# openx3.net
KiCad netlist of a schematic drawn in EAGLE
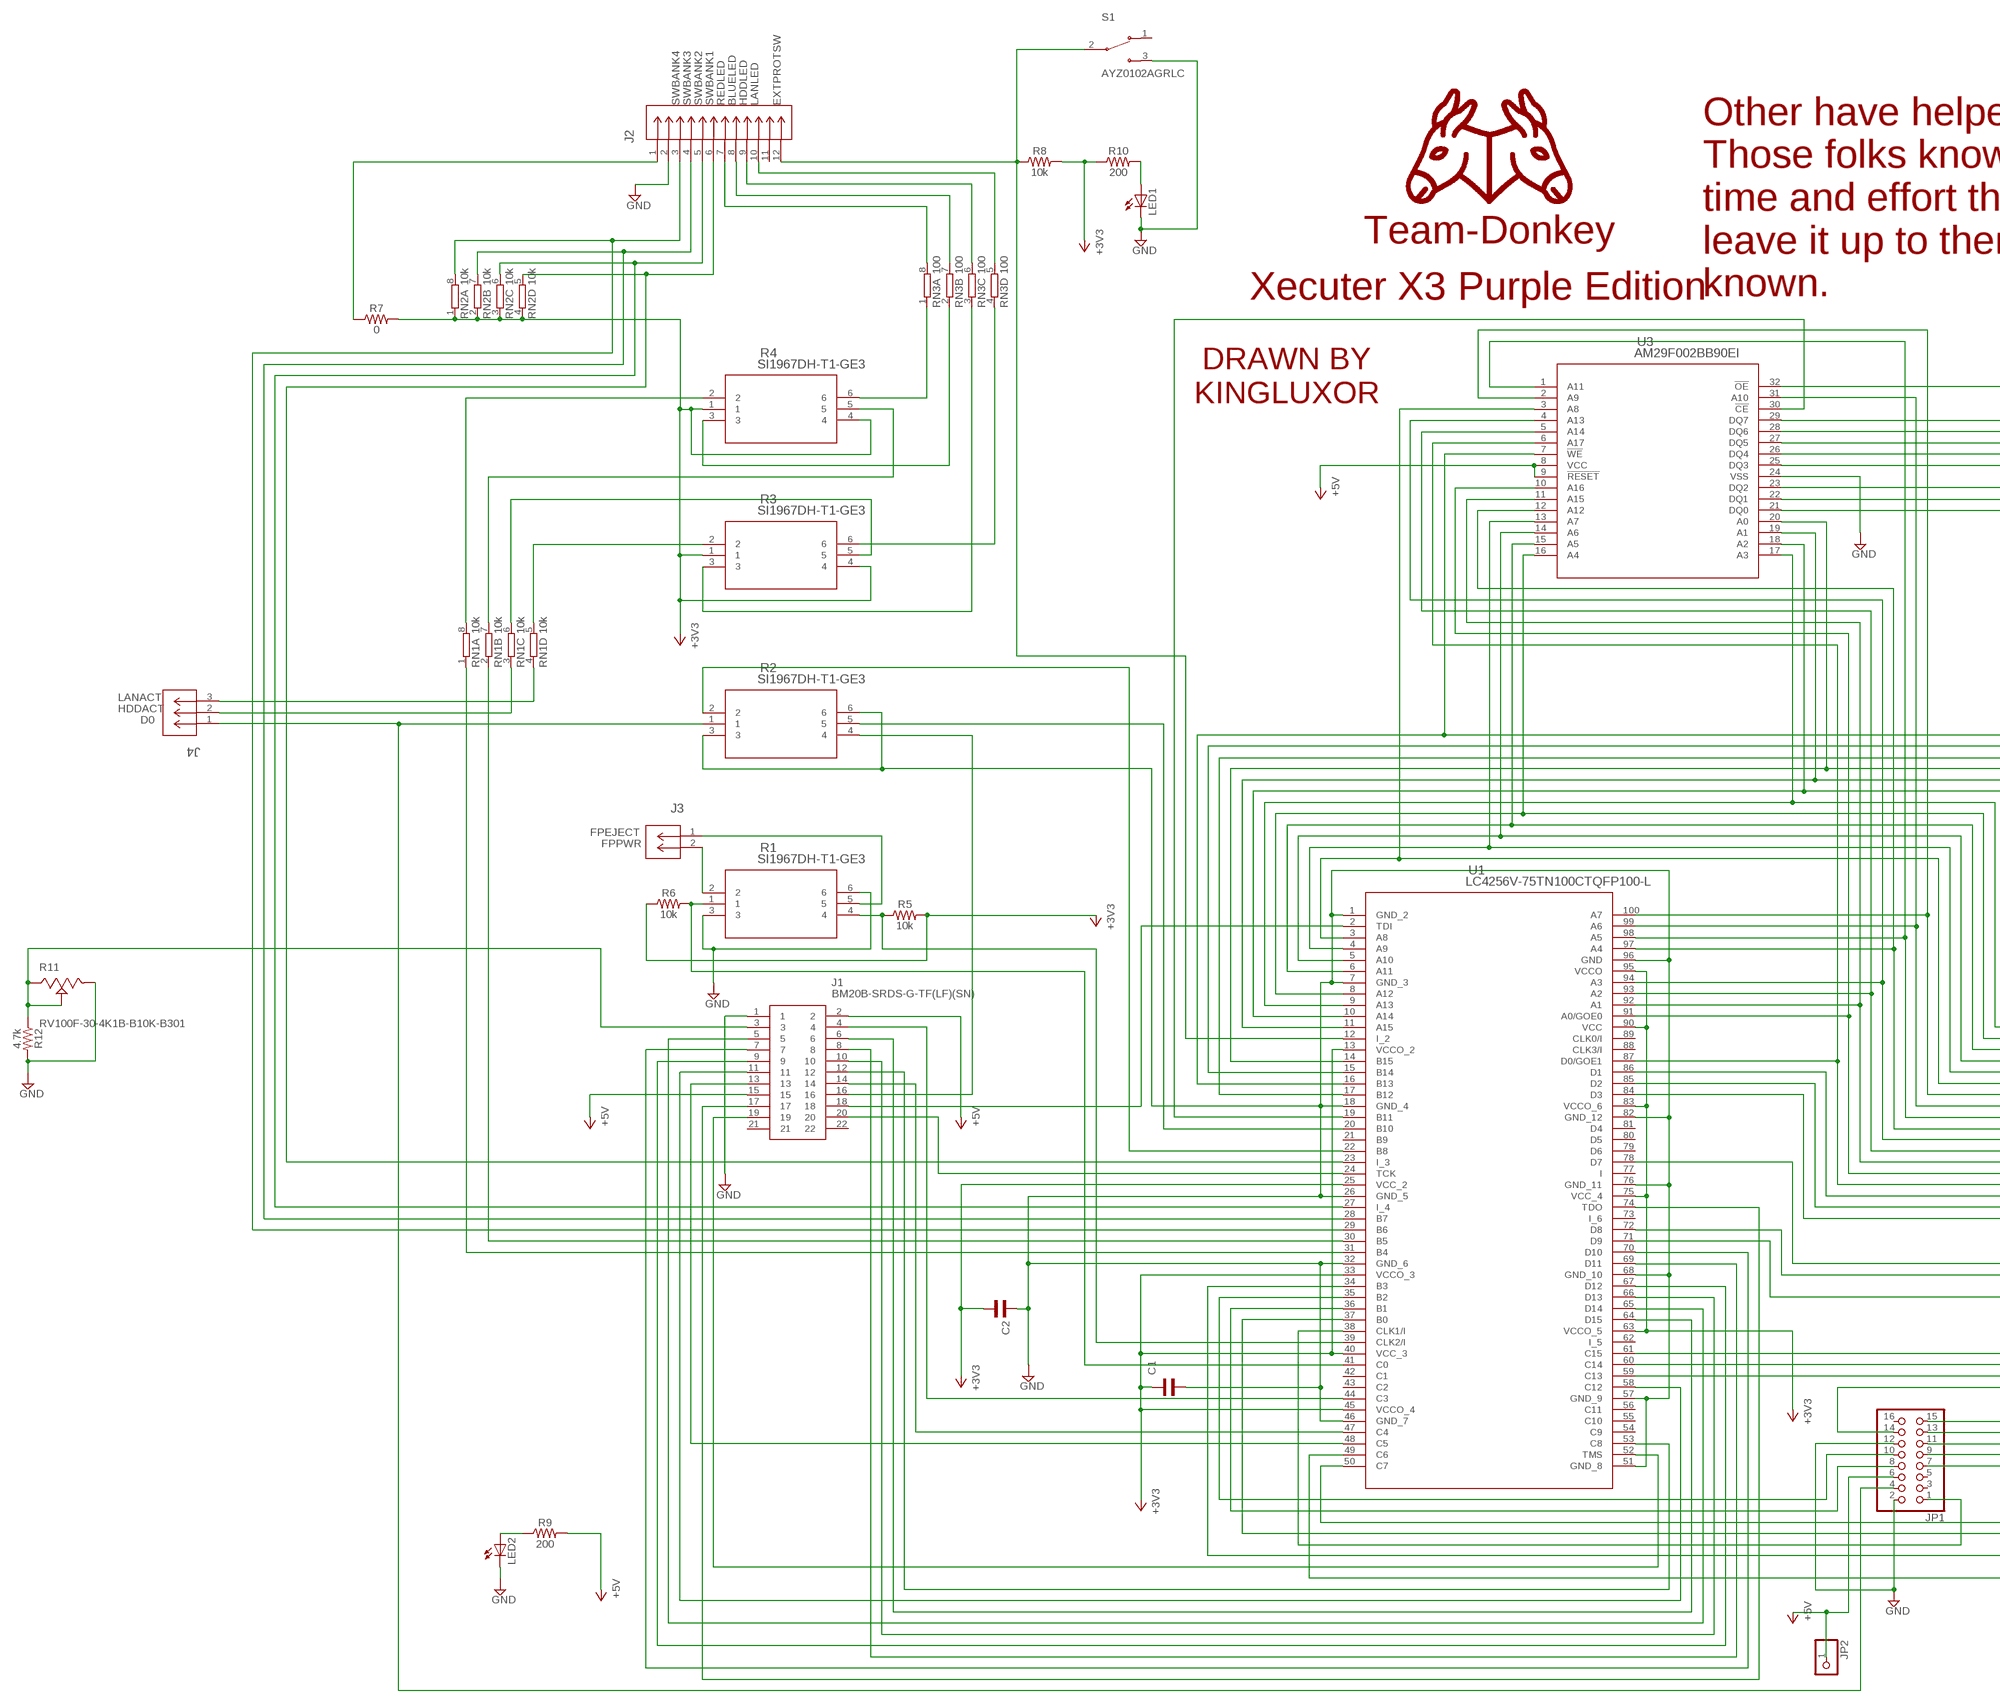
[diagram p0: schematic, sheet 1, part 1 of 2]
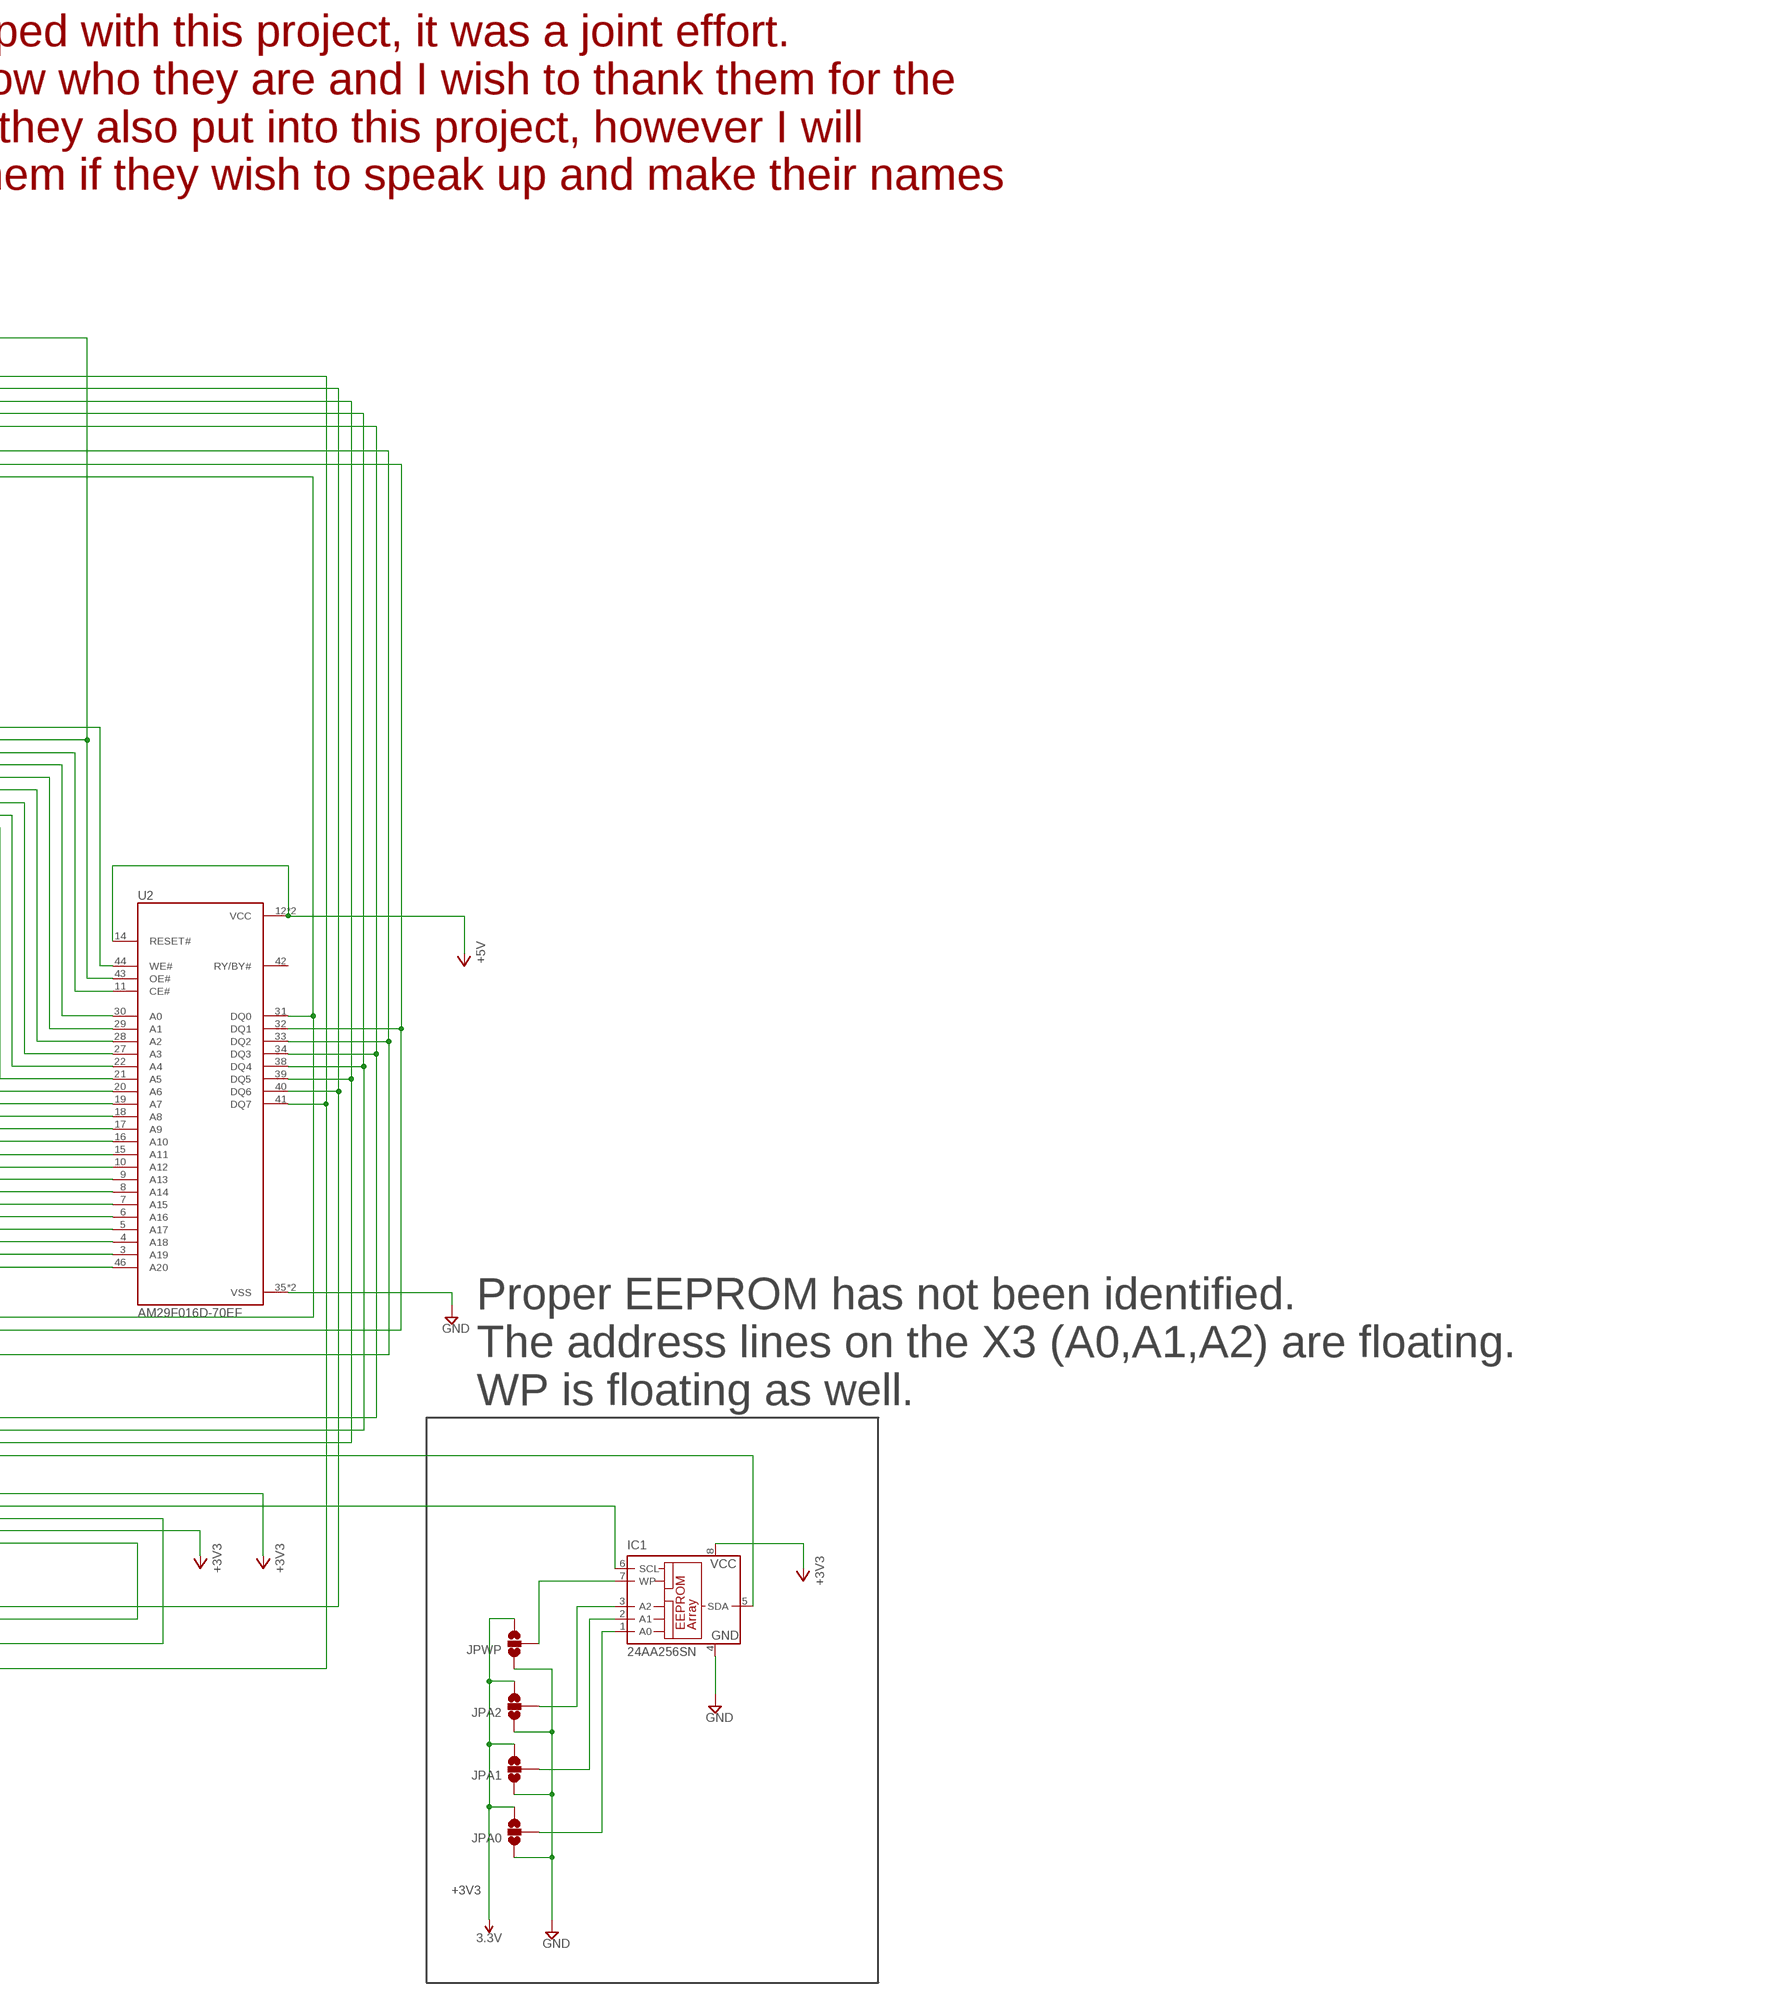
[diagram p1: schematic, sheet 1, part 2 of 2]

(export (version "E")
  (design (tool "Eeschema 10.0.6"))
  (components
    (comp (ref "C1")
      (value "WCAP-CSGP_0603_885012006001_REFLOW")
      (footprint "eagle-import:WCAP-CSGP_0603_REFLOW")
      (libsource (lib "eagle-import") (part "WCAP-CSGP_0603_REFLOW_885012006001"))
    )
    (comp (ref "C2")
      (value "WCAP-CSGP_0603_885012006001_REFLOW")
      (footprint "eagle-import:WCAP-CSGP_0603_REFLOW")
      (libsource (lib "eagle-import") (part "WCAP-CSGP_0603_REFLOW_885012006001"))
    )
    (comp (ref "IC1")
      (value "24AA256SN")
      (footprint "eagle-import:SO-08")
      (fields (field (name "MPN") "24AA256T-I/SM"))
      (libsource (lib "eagle-import") (part "24SNAA256"))
    )
    (comp (ref "J1")
      (value "BM20B-SRDS-G-TF(LF)(SN)")
      (footprint "eagle-import:BM20BSRDSGTFLFSN")
      (libsource (lib "eagle-import") (part "BM20B-SRDS-G-TF(LF)(SN)"))
    )
    (comp (ref "J2")
      (value "SM12B-SRSS-TB(LF)(SN)")
      (footprint "eagle-import:CONN_SM12B-SRSS-TB(LF)(SN)")
      (fields (field (name "COPYRIGHT") "Copyright (C) 2018 Accelerated Designs. All rights reserved"))
      (libsource (lib "eagle-import") (part "SM12B-SRSS-TB(LF)(SN)"))
    )
    (comp (ref "J3")
      (value "53398-0271")
      (footprint "eagle-import:CON00327_2")
      (fields (field (name "COPYRIGHT") "Copyright (C) 2016 Accelerated Designs. All rights reserved"))
      (libsource (lib "eagle-import") (part "53398-0271"))
    )
    (comp (ref "J4")
      (value "1734260-3")
      (footprint "eagle-import:CON3_1X3_DRM125_HPI")
      (libsource (lib "eagle-import") (part "1734260-3"))
    )
    (comp (ref "JP1")
      (value "PINHD-2X8")
      (footprint "eagle-import:2X08")
      (libsource (lib "eagle-import") (part "PINHD-2X8"))
    )
    (comp (ref "JP2")
      (value "PINHD-1X1")
      (footprint "eagle-import:1X01")
      (libsource (lib "eagle-import") (part "PINHD-1X1"))
    )
    (comp (ref "JPA0")
      (value "JUMPER-SMT_3_NO_NO-SILK")
      (footprint "eagle-import:SMT-JUMPER_3_NO_NO-SILK")
      (libsource (lib "eagle-import") (part "JUMPER-SMT_3_NO_NO-SILK"))
    )
    (comp (ref "JPA1")
      (value "JUMPER-SMT_3_NO_NO-SILK")
      (footprint "eagle-import:SMT-JUMPER_3_NO_NO-SILK")
      (libsource (lib "eagle-import") (part "JUMPER-SMT_3_NO_NO-SILK"))
    )
    (comp (ref "JPA2")
      (value "JUMPER-SMT_3_NO_NO-SILK")
      (footprint "eagle-import:SMT-JUMPER_3_NO_NO-SILK")
      (libsource (lib "eagle-import") (part "JUMPER-SMT_3_NO_NO-SILK"))
    )
    (comp (ref "JPWP")
      (value "JUMPER-SMT_3_NO_NO-SILK")
      (footprint "eagle-import:SMT-JUMPER_3_NO_NO-SILK")
      (libsource (lib "eagle-import") (part "JUMPER-SMT_3_NO_NO-SILK"))
    )
    (comp (ref "LED1")
      (value "LEDCHIPLED_0805")
      (footprint "eagle-import:CHIPLED_0805")
      (libsource (lib "eagle-import") (part "LEDCHIPLED_0805"))
    )
    (comp (ref "LED2")
      (value "LEDCHIPLED_0805")
      (footprint "eagle-import:CHIPLED_0805")
      (libsource (lib "eagle-import") (part "LEDCHIPLED_0805"))
    )
    (comp (ref "R1")
      (value "SI1967DH-T1-GE3")
      (footprint "eagle-import:TRANS_UM6J1-L")
      (fields
        (field (name "MANUFACTURER_PART_NUMBER") "UM6K31NFHATCN")
        (field (name "COPYRIGHT") "Copyright (C) 2018 Accelerated Designs. All rights reserved")
      )
      (libsource (lib "eagle-import") (part "UM6K31NFHATCNTRANS_UM6J1-L"))
    )
    (comp (ref "R2")
      (value "SI1967DH-T1-GE3")
      (footprint "eagle-import:TRANS_UM6J1-L")
      (fields
        (field (name "MANUFACTURER_PART_NUMBER") "UM6K31NFHATCN")
        (field (name "COPYRIGHT") "Copyright (C) 2018 Accelerated Designs. All rights reserved")
      )
      (libsource (lib "eagle-import") (part "UM6K31NFHATCNTRANS_UM6J1-L"))
    )
    (comp (ref "R3")
      (value "SI1967DH-T1-GE3")
      (footprint "eagle-import:TRANS_UM6J1-L")
      (fields
        (field (name "MANUFACTURER_PART_NUMBER") "UM6K31NFHATCN")
        (field (name "COPYRIGHT") "Copyright (C) 2018 Accelerated Designs. All rights reserved")
      )
      (libsource (lib "eagle-import") (part "UM6K31NFHATCNTRANS_UM6J1-L"))
    )
    (comp (ref "R4")
      (value "SI1967DH-T1-GE3")
      (footprint "eagle-import:TRANS_UM6J1-L")
      (fields
        (field (name "MANUFACTURER_PART_NUMBER") "UM6K31NFHATCN")
        (field (name "COPYRIGHT") "Copyright (C) 2018 Accelerated Designs. All rights reserved")
      )
      (libsource (lib "eagle-import") (part "UM6K31NFHATCNTRANS_UM6J1-L"))
    )
    (comp (ref "R5")
      (value "10k")
      (footprint "eagle-import:0603")
      (libsource (lib "eagle-import") (part "10KOHM-0603-1/10W-1%"))
    )
    (comp (ref "R6")
      (value "10k")
      (footprint "eagle-import:0603")
      (libsource (lib "eagle-import") (part "10KOHM-0603-1/10W-1%"))
    )
    (comp (ref "R7")
      (value "0")
      (footprint "eagle-import:0603")
      (libsource (lib "eagle-import") (part "0OHM-0603-1/10W-5%"))
    )
    (comp (ref "R8")
      (value "10k")
      (footprint "eagle-import:0603")
      (libsource (lib "eagle-import") (part "10KOHM-0603-1/10W-1%"))
    )
    (comp (ref "R9")
      (value "200")
      (footprint "eagle-import:0603")
      (libsource (lib "eagle-import") (part "200OHM-0603-1/10W-1%"))
    )
    (comp (ref "R10")
      (value "200")
      (footprint "eagle-import:0603")
      (libsource (lib "eagle-import") (part "200OHM-0603-1/10W-1%"))
    )
    (comp (ref "R11")
      (value "RV100F-30-4K1B-B10K-B301")
      (footprint "eagle-import:TRIM_RV100F-30-4K1B-B10K-B301")
      (fields (field (name "MF") "Alpha Taiwan"))
      (libsource (lib "eagle-import") (part "RV100F-30-4K1B-B10K-B301"))
    )
    (comp (ref "R12")
      (value "4.7k")
      (footprint "eagle-import:0603")
      (libsource (lib "eagle-import") (part "4.7KOHM-0603-1/10W-1%"))
    )
    (comp (ref "RN1")
      (value "10k")
      (footprint "eagle-import:0603-ARV")
      (libsource (lib "eagle-import") (part "4R-N0603-ARV"))
    )
    (comp (ref "RN2")
      (value "10k")
      (footprint "eagle-import:0603-ARV")
      (libsource (lib "eagle-import") (part "4R-N0603-ARV"))
    )
    (comp (ref "RN3")
      (value "100")
      (footprint "eagle-import:0603-ARV")
      (libsource (lib "eagle-import") (part "4R-N0603-ARV"))
    )
    (comp (ref "S1")
      (value "AYZ0102AGRLC")
      (footprint "eagle-import:SW_AYZ0102AGRLC")
      (fields (field (name "MF") "C&K"))
      (libsource (lib "eagle-import") (part "AYZ0102AGRLC"))
    )
    (comp (ref "U1")
      (value "LC4256V-75TN100CTQFP100-L")
      (footprint "eagle-import:TQFP100-L")
      (fields (field (name "MANUFACTURER_PART_NUMBER") "LC4256V-75TN100C"))
      (libsource (lib "eagle-import") (part "LC4256V-75TN100CTQFP100-L"))
    )
    (comp (ref "U2")
      (value "AM29F016D-70EF")
      (footprint "eagle-import:SOP50P2000X120-48N")
      (fields (field (name "MF") "Spansion"))
      (libsource (lib "eagle-import") (part "AM29F016D-70EF"))
    )
    (comp (ref "U3")
      (value "AM29F002BB90EI")
      (footprint "eagle-import:TS032")
      (libsource (lib "eagle-import") (part "AM29F002BB90EI"))
    )
  )
  (nets
    (net (code "1") (name "+3V3") (class "Default")
      (node (ref "C1") (pin "2") (pinfunction "2_2") (pintype "passive"))
      (node (ref "C2") (pin "1") (pinfunction "1_1") (pintype "passive"))
      (node (ref "IC1") (pin "8") (pinfunction "VCC_8") (pintype "power_in"))
      (node (ref "JP1") (pin "15") (pinfunction "15_15") (pintype "passive"))
      (node (ref "JP1") (pin "9") (pinfunction "9_9") (pintype "passive"))
      (node (ref "JPA0") (pin "3") (pinfunction "3_3") (pintype "passive"))
      (node (ref "JPA1") (pin "3") (pinfunction "3_3") (pintype "passive"))
      (node (ref "JPA2") (pin "3") (pinfunction "3_3") (pintype "passive"))
      (node (ref "JPWP") (pin "3") (pinfunction "3_3") (pintype "passive"))
      (node (ref "R10") (pin "1") (pinfunction "1_1") (pintype "passive"))
      (node (ref "R3") (pin "1") (pinfunction "1_1") (pintype "passive"))
      (node (ref "R3") (pin "4") (pinfunction "4_4") (pintype "passive"))
      (node (ref "R4") (pin "1") (pinfunction "1_1") (pintype "passive"))
      (node (ref "R4") (pin "4") (pinfunction "4_4") (pintype "passive"))
      (node (ref "R5") (pin "2") (pinfunction "2_2") (pintype "passive"))
      (node (ref "R6") (pin "1") (pinfunction "1_1") (pintype "passive"))
      (node (ref "R7") (pin "2") (pinfunction "2_2") (pintype "passive"))
      (node (ref "R8") (pin "2") (pinfunction "2_2") (pintype "passive"))
      (node (ref "RN2") (pin "1") (pinfunction "1_1") (pintype "passive"))
      (node (ref "RN2") (pin "2") (pinfunction "1_2") (pintype "passive"))
      (node (ref "RN2") (pin "3") (pinfunction "1_3") (pintype "passive"))
      (node (ref "RN2") (pin "4") (pinfunction "1_4") (pintype "passive"))
      (node (ref "U1") (pin "13") (pinfunction "VCCO_2_13") (pintype "power_in"))
      (node (ref "U1") (pin "25") (pinfunction "VCC_2_25") (pintype "power_in"))
      (node (ref "U1") (pin "33") (pinfunction "VCCO_3_33") (pintype "power_in"))
      (node (ref "U1") (pin "40") (pinfunction "VCC_3_40") (pintype "power_in"))
      (node (ref "U1") (pin "45") (pinfunction "VCCO_4_45") (pintype "power_in"))
      (node (ref "U1") (pin "63") (pinfunction "VCCO_5_63") (pintype "power_in"))
      (node (ref "U1") (pin "75") (pinfunction "VCC_4_75") (pintype "power_in"))
      (node (ref "U1") (pin "83") (pinfunction "VCCO_6_83") (pintype "power_in"))
      (node (ref "U1") (pin "90") (pinfunction "VCC_90") (pintype "power_in"))
      (node (ref "U1") (pin "95") (pinfunction "VCCO_95") (pintype "power_in"))
    )
    (net (code "2") (name "+5V") (class "Default")
      (node (ref "J1") (pin "15") (pinfunction "15_15") (pintype "bidirectional"))
      (node (ref "J1") (pin "2") (pinfunction "2_2") (pintype "bidirectional"))
      (node (ref "JP1") (pin "6") (pinfunction "6_6") (pintype "passive"))
      (node (ref "JP2") (pin "1") (pinfunction "1_1") (pintype "passive"))
      (node (ref "R9") (pin "2") (pinfunction "2_2") (pintype "passive"))
      (node (ref "U2") (pin "12") (pinfunction "VCC_12") (pintype "power_in"))
      (node (ref "U2") (pin "14") (pinfunction "RESET#_14") (pintype "input"))
      (node (ref "U2") (pin "37") (pinfunction "VCC_37") (pintype "power_in"))
      (node (ref "U3") (pin "8") (pinfunction "VCC_8") (pintype "power_in"))
      (node (ref "U3") (pin "9") (pinfunction "~{RESET}_9") (pintype "input"))
    )
    (net (code "3") (name "/BLUELED") (class "Default")
      (node (ref "J2") (pin "8") (pinfunction "8_8") (pintype "passive"))
      (node (ref "RN3") (pin "7") (pinfunction "2_7") (pintype "passive"))
    )
    (net (code "4") (name "/D0") (class "Default")
      (node (ref "J4") (pin "1") (pinfunction "1_1") (pintype "passive"))
      (node (ref "JP1") (pin "4") (pinfunction "4_4") (pintype "passive"))
      (node (ref "R2") (pin "1") (pinfunction "1_1") (pintype "passive"))
    )
    (net (code "5") (name "/EXTPROTSW") (class "Default")
      (node (ref "J2") (pin "12") (pinfunction "12_12") (pintype "passive"))
      (node (ref "R8") (pin "1") (pinfunction "1_1") (pintype "passive"))
      (node (ref "S1") (pin "2") (pinfunction "2_2") (pintype "passive"))
      (node (ref "U1") (pin "12") (pinfunction "I_2_12") (pintype "passive"))
    )
    (net (code "6") (name "/FPEJECT") (class "Default")
      (node (ref "J3") (pin "1") (pinfunction "1_1") (pintype "passive"))
      (node (ref "R1") (pin "5") (pinfunction "5_5") (pintype "passive"))
    )
    (net (code "7") (name "/FPPWR") (class "Default")
      (node (ref "J3") (pin "2") (pinfunction "2_2") (pintype "passive"))
      (node (ref "R1") (pin "2") (pinfunction "2_2") (pintype "passive"))
    )
    (net (code "8") (name "/HDDACT") (class "Default")
      (node (ref "J4") (pin "2") (pinfunction "2_2") (pintype "passive"))
      (node (ref "RN1") (pin "3") (pinfunction "1_3") (pintype "passive"))
    )
    (net (code "9") (name "/HDDLED") (class "Default")
      (node (ref "J2") (pin "9") (pinfunction "9_9") (pintype "passive"))
      (node (ref "RN3") (pin "6") (pinfunction "2_6") (pintype "passive"))
    )
    (net (code "10") (name "/LANACT") (class "Default")
      (node (ref "J4") (pin "3") (pinfunction "3_3") (pintype "passive"))
      (node (ref "RN1") (pin "4") (pinfunction "1_4") (pintype "passive"))
    )
    (net (code "11") (name "/LANLED") (class "Default")
      (node (ref "J2") (pin "10") (pinfunction "10_10") (pintype "passive"))
      (node (ref "RN3") (pin "5") (pinfunction "2_5") (pintype "passive"))
    )
    (net (code "12") (name "/REDLED") (class "Default")
      (node (ref "J2") (pin "7") (pinfunction "7_7") (pintype "passive"))
      (node (ref "RN3") (pin "8") (pinfunction "2_8") (pintype "passive"))
    )
    (net (code "13") (name "/SWBANK1") (class "Default")
      (node (ref "J2") (pin "6") (pinfunction "6_6") (pintype "passive"))
      (node (ref "RN2") (pin "5") (pinfunction "2_5") (pintype "passive"))
      (node (ref "U1") (pin "23") (pinfunction "I_3_23") (pintype "passive"))
    )
    (net (code "14") (name "/SWBANK2") (class "Default")
      (node (ref "J2") (pin "5") (pinfunction "5_5") (pintype "passive"))
      (node (ref "RN2") (pin "6") (pinfunction "2_6") (pintype "passive"))
      (node (ref "U1") (pin "27") (pinfunction "I_4_27") (pintype "passive"))
    )
    (net (code "15") (name "/SWBANK3") (class "Default")
      (node (ref "J2") (pin "4") (pinfunction "4_4") (pintype "passive"))
      (node (ref "RN2") (pin "7") (pinfunction "2_7") (pintype "passive"))
      (node (ref "U1") (pin "28") (pinfunction "B7_28") (pintype "passive"))
    )
    (net (code "16") (name "/SWBANK4") (class "Default")
      (node (ref "J2") (pin "3") (pinfunction "3_3") (pintype "passive"))
      (node (ref "RN2") (pin "8") (pinfunction "2_8") (pintype "passive"))
      (node (ref "U1") (pin "29") (pinfunction "B6_29") (pintype "passive"))
    )
    (net (code "17") (name "GND") (class "Default")
      (node (ref "C1") (pin "1") (pinfunction "1_1") (pintype "passive"))
      (node (ref "C2") (pin "2") (pinfunction "2_2") (pintype "passive"))
      (node (ref "IC1") (pin "4") (pinfunction "GND_4") (pintype "power_in"))
      (node (ref "J1") (pin "1") (pinfunction "1_1") (pintype "bidirectional"))
      (node (ref "J2") (pin "2") (pinfunction "2_2") (pintype "passive"))
      (node (ref "JP1") (pin "12") (pinfunction "12_12") (pintype "passive"))
      (node (ref "JP1") (pin "2") (pinfunction "2_2") (pintype "passive"))
      (node (ref "JPA0") (pin "1") (pinfunction "1_1") (pintype "passive"))
      (node (ref "JPA1") (pin "1") (pinfunction "1_1") (pintype "passive"))
      (node (ref "JPA2") (pin "1") (pinfunction "1_1") (pintype "passive"))
      (node (ref "JPWP") (pin "1") (pinfunction "1_1") (pintype "passive"))
      (node (ref "LED1") (pin "C") (pinfunction "C_C") (pintype "passive"))
      (node (ref "LED2") (pin "C") (pinfunction "C_C") (pintype "passive"))
      (node (ref "R1") (pin "3") (pinfunction "3_3") (pintype "passive"))
      (node (ref "R1") (pin "6") (pinfunction "6_6") (pintype "passive"))
      (node (ref "R11") (pin "3") (pinfunction "3_3") (pintype "passive"))
      (node (ref "R12") (pin "2") (pinfunction "2_2") (pintype "passive"))
      (node (ref "R2") (pin "3") (pinfunction "3_3") (pintype "passive"))
      (node (ref "R2") (pin "6") (pinfunction "6_6") (pintype "passive"))
      (node (ref "S1") (pin "3") (pinfunction "3_3") (pintype "passive"))
      (node (ref "U1") (pin "1") (pinfunction "GND_2_1") (pintype "power_in"))
      (node (ref "U1") (pin "18") (pinfunction "GND_4_18") (pintype "power_in"))
      (node (ref "U1") (pin "26") (pinfunction "GND_5_26") (pintype "power_in"))
      (node (ref "U1") (pin "32") (pinfunction "GND_6_32") (pintype "power_in"))
      (node (ref "U1") (pin "46") (pinfunction "GND_7_46") (pintype "power_in"))
      (node (ref "U1") (pin "51") (pinfunction "GND_8_51") (pintype "power_in"))
      (node (ref "U1") (pin "57") (pinfunction "GND_9_57") (pintype "power_in"))
      (node (ref "U1") (pin "68") (pinfunction "GND_10_68") (pintype "power_in"))
      (node (ref "U1") (pin "7") (pinfunction "GND_3_7") (pintype "power_in"))
      (node (ref "U1") (pin "76") (pinfunction "GND_11_76") (pintype "power_in"))
      (node (ref "U1") (pin "82") (pinfunction "GND_12_82") (pintype "power_in"))
      (node (ref "U1") (pin "96") (pinfunction "GND_96") (pintype "power_in"))
      (node (ref "U2") (pin "35") (pinfunction "VSS_35") (pintype "power_in"))
      (node (ref "U2") (pin "36") (pinfunction "VSS_36") (pintype "power_in"))
      (node (ref "U3") (pin "24") (pinfunction "VSS_24") (pintype "power_in"))
    )
    (net (code "18") (name "Net-(IC1-A0)") (class "Default")
      (node (ref "IC1") (pin "1") (pinfunction "A0_1") (pintype "input"))
      (node (ref "JPA0") (pin "2") (pinfunction "2_2") (pintype "passive"))
    )
    (net (code "19") (name "Net-(IC1-A1)") (class "Default")
      (node (ref "IC1") (pin "2") (pinfunction "A1_2") (pintype "input"))
      (node (ref "JPA1") (pin "2") (pinfunction "2_2") (pintype "passive"))
    )
    (net (code "20") (name "Net-(IC1-A2)") (class "Default")
      (node (ref "IC1") (pin "3") (pinfunction "A2_3") (pintype "input"))
      (node (ref "JPA2") (pin "2") (pinfunction "2_2") (pintype "passive"))
    )
    (net (code "21") (name "Net-(IC1-SCL)") (class "Default")
      (node (ref "IC1") (pin "6") (pinfunction "SCL_6") (pintype "input"))
      (node (ref "JP1") (pin "13") (pinfunction "13_13") (pintype "passive"))
    )
    (net (code "22") (name "Net-(IC1-SDA)") (class "Default")
      (node (ref "IC1") (pin "5") (pinfunction "SDA_5") (pintype "bidirectional"))
      (node (ref "JP1") (pin "14") (pinfunction "14_14") (pintype "passive"))
    )
    (net (code "23") (name "Net-(IC1-WP)") (class "Default")
      (node (ref "IC1") (pin "7") (pinfunction "WP_7") (pintype "input"))
      (node (ref "JPWP") (pin "2") (pinfunction "2_2") (pintype "passive"))
    )
    (net (code "24") (name "Net-(J1-Pad3)") (class "Default")
      (node (ref "J1") (pin "3") (pinfunction "3_3") (pintype "bidirectional"))
      (node (ref "R11") (pin "1") (pinfunction "1_1") (pintype "passive"))
      (node (ref "R11") (pin "2") (pinfunction "2_2") (pintype "passive"))
      (node (ref "R12") (pin "1") (pinfunction "1_1") (pintype "passive"))
    )
    (net (code "25") (name "Net-(J1-Pad16)") (class "Default")
      (node (ref "J1") (pin "16") (pinfunction "16_16") (pintype "bidirectional"))
      (node (ref "R2") (pin "4") (pinfunction "4_4") (pintype "passive"))
    )
    (net (code "26") (name "Net-(J2-Pad1)") (class "Default")
      (node (ref "J2") (pin "1") (pinfunction "1_1") (pintype "passive"))
      (node (ref "R7") (pin "1") (pinfunction "1_1") (pintype "passive"))
    )
    (net (code "27") (name "Net-(LED1-PadA)") (class "Default")
      (node (ref "LED1") (pin "A") (pinfunction "A_A") (pintype "passive"))
      (node (ref "R10") (pin "2") (pinfunction "2_2") (pintype "passive"))
    )
    (net (code "28") (name "Net-(LED2-PadA)") (class "Default")
      (node (ref "LED2") (pin "A") (pinfunction "A_A") (pintype "passive"))
      (node (ref "R9") (pin "1") (pinfunction "1_1") (pintype "passive"))
    )
    (net (code "29") (name "Net-(R4-Pad6)") (class "Default")
      (node (ref "R4") (pin "6") (pinfunction "6_6") (pintype "passive"))
      (node (ref "RN3") (pin "1") (pinfunction "1_1") (pintype "passive"))
    )
    (net (code "30") (name "Net-(RN1A-2)") (class "Default")
      (node (ref "R4") (pin "2") (pinfunction "2_2") (pintype "passive"))
      (node (ref "RN1") (pin "8") (pinfunction "2_8") (pintype "passive"))
    )
    (net (code "31") (name "Net-(RN1B-1)") (class "Default")
      (node (ref "RN1") (pin "2") (pinfunction "1_2") (pintype "passive"))
      (node (ref "U1") (pin "30") (pinfunction "B5_30") (pintype "passive"))
    )
    (net (code "32") (name "Net-(RN1B-2)") (class "Default")
      (node (ref "R4") (pin "5") (pinfunction "5_5") (pintype "passive"))
      (node (ref "RN1") (pin "7") (pinfunction "2_7") (pintype "passive"))
    )
    (net (code "33") (name "Net-(RN1C-2)") (class "Default")
      (node (ref "R3") (pin "5") (pinfunction "5_5") (pintype "passive"))
      (node (ref "RN1") (pin "6") (pinfunction "2_6") (pintype "passive"))
    )
    (net (code "34") (name "Net-(RN1D-2)") (class "Default")
      (node (ref "R3") (pin "2") (pinfunction "2_2") (pintype "passive"))
      (node (ref "RN1") (pin "5") (pinfunction "2_5") (pintype "passive"))
    )
    (net (code "35") (name "Net-(RN3B-1)") (class "Default")
      (node (ref "R4") (pin "3") (pinfunction "3_3") (pintype "passive"))
      (node (ref "RN3") (pin "2") (pinfunction "1_2") (pintype "passive"))
    )
    (net (code "36") (name "Net-(RN3C-1)") (class "Default")
      (node (ref "R3") (pin "3") (pinfunction "3_3") (pintype "passive"))
      (node (ref "RN3") (pin "3") (pinfunction "1_3") (pintype "passive"))
    )
    (net (code "37") (name "Net-(RN3D-1)") (class "Default")
      (node (ref "R3") (pin "6") (pinfunction "6_6") (pintype "passive"))
      (node (ref "RN3") (pin "4") (pinfunction "1_4") (pintype "passive"))
    )
    (net (code "38") (name "Net-(U1-A0{slash}GOE0)") (class "Default")
      (node (ref "U1") (pin "91") (pinfunction "A0/GOE0_91") (pintype "passive"))
      (node (ref "U2") (pin "6") (pinfunction "A16_6") (pintype "input"))
      (node (ref "U3") (pin "10") (pinfunction "A16_10") (pintype "input"))
    )
    (net (code "39") (name "Net-(U1-A1)") (class "Default")
      (node (ref "U1") (pin "92") (pinfunction "A1_92") (pintype "passive"))
      (node (ref "U2") (pin "7") (pinfunction "A15_7") (pintype "input"))
      (node (ref "U3") (pin "11") (pinfunction "A15_11") (pintype "input"))
    )
    (net (code "40") (name "Net-(U1-A2)") (class "Default")
      (node (ref "U1") (pin "93") (pinfunction "A2_93") (pintype "passive"))
      (node (ref "U2") (pin "8") (pinfunction "A14_8") (pintype "input"))
      (node (ref "U3") (pin "5") (pinfunction "A14_5") (pintype "input"))
    )
    (net (code "41") (name "Net-(U1-A3)") (class "Default")
      (node (ref "U1") (pin "94") (pinfunction "A3_94") (pintype "passive"))
      (node (ref "U2") (pin "9") (pinfunction "A13_9") (pintype "input"))
      (node (ref "U3") (pin "4") (pinfunction "A13_4") (pintype "input"))
    )
    (net (code "42") (name "Net-(U1-A4)") (class "Default")
      (node (ref "U1") (pin "97") (pinfunction "A4_97") (pintype "passive"))
      (node (ref "U2") (pin "10") (pinfunction "A12_10") (pintype "input"))
      (node (ref "U3") (pin "12") (pinfunction "A12_12") (pintype "input"))
    )
    (net (code "43") (name "Net-(U1-A5)") (class "Default")
      (node (ref "U1") (pin "98") (pinfunction "A5_98") (pintype "passive"))
      (node (ref "U2") (pin "15") (pinfunction "A11_15") (pintype "input"))
      (node (ref "U3") (pin "1") (pinfunction "A11_1") (pintype "input"))
    )
    (net (code "44") (name "Net-(U1-A6)") (class "Default")
      (node (ref "U1") (pin "99") (pinfunction "A6_99") (pintype "passive"))
      (node (ref "U2") (pin "16") (pinfunction "A10_16") (pintype "input"))
      (node (ref "U3") (pin "31") (pinfunction "A10_31") (pintype "input"))
    )
    (net (code "45") (name "Net-(U1-A7)") (class "Default")
      (node (ref "U1") (pin "100") (pinfunction "A7_100") (pintype "passive"))
      (node (ref "U2") (pin "17") (pinfunction "A9_17") (pintype "input"))
      (node (ref "U3") (pin "2") (pinfunction "A9_2") (pintype "input"))
    )
    (net (code "46") (name "Net-(U1-A8)") (class "Default")
      (node (ref "U1") (pin "3") (pinfunction "A8_3") (pintype "passive"))
      (node (ref "U2") (pin "18") (pinfunction "A8_18") (pintype "input"))
      (node (ref "U3") (pin "3") (pinfunction "A8_3") (pintype "input"))
    )
    (net (code "47") (name "Net-(U1-A9)") (class "Default")
      (node (ref "U1") (pin "4") (pinfunction "A9_4") (pintype "passive"))
      (node (ref "U2") (pin "19") (pinfunction "A7_19") (pintype "input"))
      (node (ref "U3") (pin "13") (pinfunction "A7_13") (pintype "input"))
    )
    (net (code "48") (name "Net-(U1-A10)") (class "Default")
      (node (ref "U1") (pin "5") (pinfunction "A10_5") (pintype "passive"))
      (node (ref "U2") (pin "20") (pinfunction "A6_20") (pintype "input"))
      (node (ref "U3") (pin "14") (pinfunction "A6_14") (pintype "input"))
    )
    (net (code "49") (name "Net-(U1-A11)") (class "Default")
      (node (ref "U1") (pin "6") (pinfunction "A11_6") (pintype "passive"))
      (node (ref "U2") (pin "21") (pinfunction "A5_21") (pintype "input"))
      (node (ref "U3") (pin "15") (pinfunction "A5_15") (pintype "input"))
    )
    (net (code "50") (name "Net-(U1-A12)") (class "Default")
      (node (ref "U1") (pin "8") (pinfunction "A12_8") (pintype "passive"))
      (node (ref "U2") (pin "22") (pinfunction "A4_22") (pintype "input"))
      (node (ref "U3") (pin "16") (pinfunction "A4_16") (pintype "input"))
    )
    (net (code "51") (name "Net-(U1-A13)") (class "Default")
      (node (ref "U1") (pin "9") (pinfunction "A13_9") (pintype "passive"))
      (node (ref "U2") (pin "27") (pinfunction "A3_27") (pintype "input"))
      (node (ref "U3") (pin "17") (pinfunction "A3_17") (pintype "input"))
    )
    (net (code "52") (name "Net-(U1-A14)") (class "Default")
      (node (ref "U1") (pin "10") (pinfunction "A14_10") (pintype "passive"))
      (node (ref "U2") (pin "28") (pinfunction "A2_28") (pintype "input"))
      (node (ref "U3") (pin "18") (pinfunction "A2_18") (pintype "input"))
    )
    (net (code "53") (name "Net-(U1-A15)") (class "Default")
      (node (ref "U1") (pin "11") (pinfunction "A15_11") (pintype "passive"))
      (node (ref "U2") (pin "29") (pinfunction "A1_29") (pintype "input"))
      (node (ref "U3") (pin "19") (pinfunction "A1_19") (pintype "input"))
    )
    (net (code "54") (name "Net-(U1-B0)") (class "Default")
      (node (ref "JP1") (pin "7") (pinfunction "7_7") (pintype "passive"))
      (node (ref "U1") (pin "37") (pinfunction "B0_37") (pintype "passive"))
    )
    (net (code "55") (name "Net-(U1-B1)") (class "Default")
      (node (ref "JP1") (pin "8") (pinfunction "8_8") (pintype "passive"))
      (node (ref "U1") (pin "36") (pinfunction "B1_36") (pintype "passive"))
    )
    (net (code "56") (name "Net-(U1-B2)") (class "Default")
      (node (ref "JP1") (pin "10") (pinfunction "10_10") (pintype "passive"))
      (node (ref "U1") (pin "35") (pinfunction "B2_35") (pintype "passive"))
    )
    (net (code "57") (name "Net-(U1-B3)") (class "Default")
      (node (ref "JP1") (pin "11") (pinfunction "11_11") (pintype "passive"))
      (node (ref "U1") (pin "34") (pinfunction "B3_34") (pintype "passive"))
    )
    (net (code "58") (name "Net-(U1-B4)") (class "Default")
      (node (ref "RN1") (pin "1") (pinfunction "1_1") (pintype "passive"))
      (node (ref "U1") (pin "31") (pinfunction "B4_31") (pintype "passive"))
    )
    (net (code "59") (name "Net-(U1-B8)") (class "Default")
      (node (ref "R2") (pin "2") (pinfunction "2_2") (pintype "passive"))
      (node (ref "U1") (pin "22") (pinfunction "B8_22") (pintype "passive"))
    )
    (net (code "60") (name "Net-(U1-B10)") (class "Default")
      (node (ref "R2") (pin "5") (pinfunction "5_5") (pintype "passive"))
      (node (ref "U1") (pin "20") (pinfunction "B10_20") (pintype "passive"))
    )
    (net (code "61") (name "Net-(U1-B11)") (class "Default")
      (node (ref "U1") (pin "19") (pinfunction "B11_19") (pintype "passive"))
      (node (ref "U3") (pin "30") (pinfunction "~{CE}_30") (pintype "input"))
    )
    (net (code "62") (name "Net-(U1-B12)") (class "Default")
      (node (ref "U1") (pin "17") (pinfunction "B12_17") (pintype "passive"))
      (node (ref "U2") (pin "11") (pinfunction "CE#_11") (pintype "input"))
    )
    (net (code "63") (name "Net-(U1-B13)") (class "Default")
      (node (ref "U1") (pin "16") (pinfunction "B13_16") (pintype "passive"))
      (node (ref "U2") (pin "44") (pinfunction "WE#_44") (pintype "input"))
      (node (ref "U3") (pin "7") (pinfunction "~{WE}_7") (pintype "input"))
    )
    (net (code "64") (name "Net-(U1-B14)") (class "Default")
      (node (ref "U1") (pin "15") (pinfunction "B14_15") (pintype "passive"))
      (node (ref "U2") (pin "43") (pinfunction "OE#_43") (pintype "input"))
      (node (ref "U3") (pin "32") (pinfunction "~{OE}_32") (pintype "input"))
    )
    (net (code "65") (name "Net-(U1-B15)") (class "Default")
      (node (ref "U1") (pin "14") (pinfunction "B15_14") (pintype "passive"))
      (node (ref "U2") (pin "30") (pinfunction "A0_30") (pintype "input"))
      (node (ref "U3") (pin "20") (pinfunction "A0_20") (pintype "input"))
    )
    (net (code "66") (name "Net-(U1-C0)") (class "Default")
      (node (ref "R1") (pin "1") (pinfunction "1_1") (pintype "passive"))
      (node (ref "R6") (pin "2") (pinfunction "2_2") (pintype "passive"))
      (node (ref "U1") (pin "41") (pinfunction "C0_41") (pintype "passive"))
    )
    (net (code "67") (name "Net-(U1-C3)") (class "Default")
      (node (ref "J1") (pin "4") (pinfunction "4_4") (pintype "bidirectional"))
      (node (ref "U1") (pin "44") (pinfunction "C3_44") (pintype "passive"))
    )
    (net (code "68") (name "Net-(U1-C4)") (class "Default")
      (node (ref "J1") (pin "14") (pinfunction "14_14") (pintype "bidirectional"))
      (node (ref "U1") (pin "47") (pinfunction "C4_47") (pintype "passive"))
    )
    (net (code "69") (name "Net-(U1-C5)") (class "Default")
      (node (ref "J1") (pin "13") (pinfunction "13_13") (pintype "bidirectional"))
      (node (ref "U1") (pin "48") (pinfunction "C5_48") (pintype "passive"))
    )
    (net (code "70") (name "Net-(U1-C6)") (class "Default")
      (node (ref "U1") (pin "49") (pinfunction "C6_49") (pintype "passive"))
      (node (ref "U2") (pin "41") (pinfunction "DQ7_41") (pintype "bidirectional"))
      (node (ref "U3") (pin "29") (pinfunction "DQ7_29") (pintype "bidirectional"))
    )
    (net (code "71") (name "Net-(U1-C7)") (class "Default")
      (node (ref "U1") (pin "50") (pinfunction "C7_50") (pintype "passive"))
      (node (ref "U2") (pin "40") (pinfunction "DQ6_40") (pintype "bidirectional"))
      (node (ref "U3") (pin "28") (pinfunction "DQ6_28") (pintype "bidirectional"))
    )
    (net (code "72") (name "Net-(U1-C8)") (class "Default")
      (node (ref "J1") (pin "12") (pinfunction "12_12") (pintype "bidirectional"))
      (node (ref "U1") (pin "53") (pinfunction "C8_53") (pintype "passive"))
    )
    (net (code "73") (name "Net-(U1-C12)") (class "Default")
      (node (ref "J1") (pin "11") (pinfunction "11_11") (pintype "bidirectional"))
      (node (ref "U1") (pin "58") (pinfunction "C12_58") (pintype "passive"))
    )
    (net (code "74") (name "Net-(U1-C13)") (class "Default")
      (node (ref "U1") (pin "59") (pinfunction "C13_59") (pintype "passive"))
      (node (ref "U2") (pin "39") (pinfunction "DQ5_39") (pintype "bidirectional"))
      (node (ref "U3") (pin "27") (pinfunction "DQ5_27") (pintype "bidirectional"))
    )
    (net (code "75") (name "Net-(U1-C14)") (class "Default")
      (node (ref "U1") (pin "60") (pinfunction "C14_60") (pintype "passive"))
      (node (ref "U2") (pin "38") (pinfunction "DQ4_38") (pintype "bidirectional"))
      (node (ref "U3") (pin "26") (pinfunction "DQ4_26") (pintype "bidirectional"))
    )
    (net (code "76") (name "Net-(U1-C15)") (class "Default")
      (node (ref "U1") (pin "61") (pinfunction "C15_61") (pintype "passive"))
      (node (ref "U2") (pin "34") (pinfunction "DQ3_34") (pintype "bidirectional"))
      (node (ref "U3") (pin "25") (pinfunction "DQ3_25") (pintype "bidirectional"))
    )
    (net (code "77") (name "Net-(U1-CLK1{slash}I)") (class "Default")
      (node (ref "JP1") (pin "1") (pinfunction "1_1") (pintype "passive"))
      (node (ref "U1") (pin "38") (pinfunction "CLK1/I_38") (pintype "passive"))
    )
    (net (code "78") (name "Net-(U1-CLK2{slash}I)") (class "Default")
      (node (ref "R1") (pin "4") (pinfunction "4_4") (pintype "passive"))
      (node (ref "R5") (pin "1") (pinfunction "1_1") (pintype "passive"))
      (node (ref "U1") (pin "39") (pinfunction "CLK2/I_39") (pintype "passive"))
    )
    (net (code "79") (name "Net-(U1-D0{slash}GOE1)") (class "Default")
      (node (ref "U1") (pin "87") (pinfunction "D0/GOE1_87") (pintype "passive"))
      (node (ref "U2") (pin "5") (pinfunction "A17_5") (pintype "input"))
      (node (ref "U3") (pin "6") (pinfunction "A17_6") (pintype "input"))
    )
    (net (code "80") (name "Net-(U1-D1)") (class "Default")
      (node (ref "U1") (pin "86") (pinfunction "D1_86") (pintype "passive"))
      (node (ref "U2") (pin "4") (pinfunction "A18_4") (pintype "input"))
    )
    (net (code "81") (name "Net-(U1-D2)") (class "Default")
      (node (ref "U1") (pin "85") (pinfunction "D2_85") (pintype "passive"))
      (node (ref "U2") (pin "3") (pinfunction "A19_3") (pintype "input"))
    )
    (net (code "82") (name "Net-(U1-D3)") (class "Default")
      (node (ref "U1") (pin "84") (pinfunction "D3_84") (pintype "passive"))
      (node (ref "U2") (pin "46") (pinfunction "A20_46") (pintype "input"))
    )
    (net (code "83") (name "Net-(U1-D7)") (class "Default")
      (node (ref "U1") (pin "78") (pinfunction "D7_78") (pintype "passive"))
      (node (ref "U2") (pin "31") (pinfunction "DQ0_31") (pintype "bidirectional"))
      (node (ref "U3") (pin "21") (pinfunction "DQ0_21") (pintype "bidirectional"))
    )
    (net (code "84") (name "Net-(U1-D8)") (class "Default")
      (node (ref "U1") (pin "72") (pinfunction "D8_72") (pintype "passive"))
      (node (ref "U2") (pin "32") (pinfunction "DQ1_32") (pintype "bidirectional"))
      (node (ref "U3") (pin "22") (pinfunction "DQ1_22") (pintype "bidirectional"))
    )
    (net (code "85") (name "Net-(U1-D9)") (class "Default")
      (node (ref "U1") (pin "71") (pinfunction "D9_71") (pintype "passive"))
      (node (ref "U2") (pin "33") (pinfunction "DQ2_33") (pintype "bidirectional"))
      (node (ref "U3") (pin "23") (pinfunction "DQ2_23") (pintype "bidirectional"))
    )
    (net (code "86") (name "Net-(U1-D10)") (class "Default")
      (node (ref "J1") (pin "7") (pinfunction "7_7") (pintype "bidirectional"))
      (node (ref "U1") (pin "70") (pinfunction "D10_70") (pintype "passive"))
    )
    (net (code "87") (name "Net-(U1-D11)") (class "Default")
      (node (ref "J1") (pin "8") (pinfunction "8_8") (pintype "bidirectional"))
      (node (ref "U1") (pin "69") (pinfunction "D11_69") (pintype "passive"))
    )
    (net (code "88") (name "Net-(U1-D12)") (class "Default")
      (node (ref "J1") (pin "9") (pinfunction "9_9") (pintype "bidirectional"))
      (node (ref "U1") (pin "67") (pinfunction "D12_67") (pintype "passive"))
    )
    (net (code "89") (name "Net-(U1-D13)") (class "Default")
      (node (ref "J1") (pin "10") (pinfunction "10_10") (pintype "bidirectional"))
      (node (ref "U1") (pin "66") (pinfunction "D13_66") (pintype "passive"))
    )
    (net (code "90") (name "Net-(U1-D14)") (class "Default")
      (node (ref "J1") (pin "5") (pinfunction "5_5") (pintype "bidirectional"))
      (node (ref "U1") (pin "65") (pinfunction "D14_65") (pintype "passive"))
    )
    (net (code "91") (name "Net-(U1-D15)") (class "Default")
      (node (ref "J1") (pin "6") (pinfunction "6_6") (pintype "bidirectional"))
      (node (ref "U1") (pin "64") (pinfunction "D15_64") (pintype "passive"))
    )
    (net (code "92") (name "Net-(U1-TCK)") (class "Default")
      (node (ref "J1") (pin "20") (pinfunction "20_20") (pintype "bidirectional"))
      (node (ref "U1") (pin "24") (pinfunction "TCK_24") (pintype "passive"))
    )
    (net (code "93") (name "Net-(U1-TDI)") (class "Default")
      (node (ref "J1") (pin "18") (pinfunction "18_18") (pintype "bidirectional"))
      (node (ref "U1") (pin "2") (pinfunction "TDI_2") (pintype "passive"))
    )
    (net (code "94") (name "Net-(U1-TDO)") (class "Default")
      (node (ref "J1") (pin "17") (pinfunction "17_17") (pintype "bidirectional"))
      (node (ref "U1") (pin "74") (pinfunction "TDO_74") (pintype "passive"))
    )
    (net (code "95") (name "Net-(U1-TMS)") (class "Default")
      (node (ref "J1") (pin "19") (pinfunction "19_19") (pintype "bidirectional"))
      (node (ref "U1") (pin "52") (pinfunction "TMS_52") (pintype "passive"))
    )
    (net (code "96") (name "unconnected-(J1-Pad21)") (class "Default")
      (node (ref "J1") (pin "21") (pinfunction "21_21") (pintype "bidirectional"))
    )
    (net (code "97") (name "unconnected-(J1-Pad22)") (class "Default")
      (node (ref "J1") (pin "22") (pinfunction "22_22") (pintype "bidirectional"))
    )
    (net (code "98") (name "unconnected-(J2-Pad11)") (class "Default")
      (node (ref "J2") (pin "11") (pinfunction "11_11") (pintype "passive"))
    )
    (net (code "99") (name "unconnected-(JP1-Pad3)") (class "Default")
      (node (ref "JP1") (pin "3") (pinfunction "3_3") (pintype "passive"))
    )
    (net (code "100") (name "unconnected-(JP1-Pad5)") (class "Default")
      (node (ref "JP1") (pin "5") (pinfunction "5_5") (pintype "passive"))
    )
    (net (code "101") (name "unconnected-(JP1-Pad16)") (class "Default")
      (node (ref "JP1") (pin "16") (pinfunction "16_16") (pintype "passive"))
    )
    (net (code "102") (name "unconnected-(S1-Pad1)") (class "Default")
      (node (ref "S1") (pin "1") (pinfunction "1_1") (pintype "passive"))
    )
    (net (code "103") (name "unconnected-(U1-B9-Pad21)") (class "Default")
      (node (ref "U1") (pin "21") (pinfunction "B9_21") (pintype "passive"))
    )
    (net (code "104") (name "unconnected-(U1-C1-Pad42)") (class "Default")
      (node (ref "U1") (pin "42") (pinfunction "C1_42") (pintype "passive"))
    )
    (net (code "105") (name "unconnected-(U1-C2-Pad43)") (class "Default")
      (node (ref "U1") (pin "43") (pinfunction "C2_43") (pintype "passive"))
    )
    (net (code "106") (name "unconnected-(U1-C9-Pad54)") (class "Default")
      (node (ref "U1") (pin "54") (pinfunction "C9_54") (pintype "passive"))
    )
    (net (code "107") (name "unconnected-(U1-C10-Pad55)") (class "Default")
      (node (ref "U1") (pin "55") (pinfunction "C10_55") (pintype "passive"))
    )
    (net (code "108") (name "unconnected-(U1-C11-Pad56)") (class "Default")
      (node (ref "U1") (pin "56") (pinfunction "C11_56") (pintype "passive"))
    )
    (net (code "109") (name "unconnected-(U1-CLK0{slash}I-Pad89)") (class "Default")
      (node (ref "U1") (pin "89") (pinfunction "CLK0/I_89") (pintype "passive"))
    )
    (net (code "110") (name "unconnected-(U1-CLK3{slash}I-Pad88)") (class "Default")
      (node (ref "U1") (pin "88") (pinfunction "CLK3/I_88") (pintype "passive"))
    )
    (net (code "111") (name "unconnected-(U1-D4-Pad81)") (class "Default")
      (node (ref "U1") (pin "81") (pinfunction "D4_81") (pintype "passive"))
    )
    (net (code "112") (name "unconnected-(U1-D5-Pad80)") (class "Default")
      (node (ref "U1") (pin "80") (pinfunction "D5_80") (pintype "passive"))
    )
    (net (code "113") (name "unconnected-(U1-D6-Pad79)") (class "Default")
      (node (ref "U1") (pin "79") (pinfunction "D6_79") (pintype "passive"))
    )
    (net (code "114") (name "unconnected-(U1-I-Pad77)") (class "Default")
      (node (ref "U1") (pin "77") (pinfunction "I_77") (pintype "passive"))
    )
    (net (code "115") (name "unconnected-(U1-I_5-Pad62)") (class "Default")
      (node (ref "U1") (pin "62") (pinfunction "I_5_62") (pintype "passive"))
    )
    (net (code "116") (name "unconnected-(U1-I_6-Pad73)") (class "Default")
      (node (ref "U1") (pin "73") (pinfunction "I_6_73") (pintype "passive"))
    )
    (net (code "117") (name "unconnected-(U2-RY{slash}BY#-Pad42)") (class "Default")
      (node (ref "U2") (pin "42") (pinfunction "RY/BY#_42") (pintype "output"))
    )
  )
)
